# lcdPCB_schematic.net
KiCad netlist of a schematic drawn in EAGLE
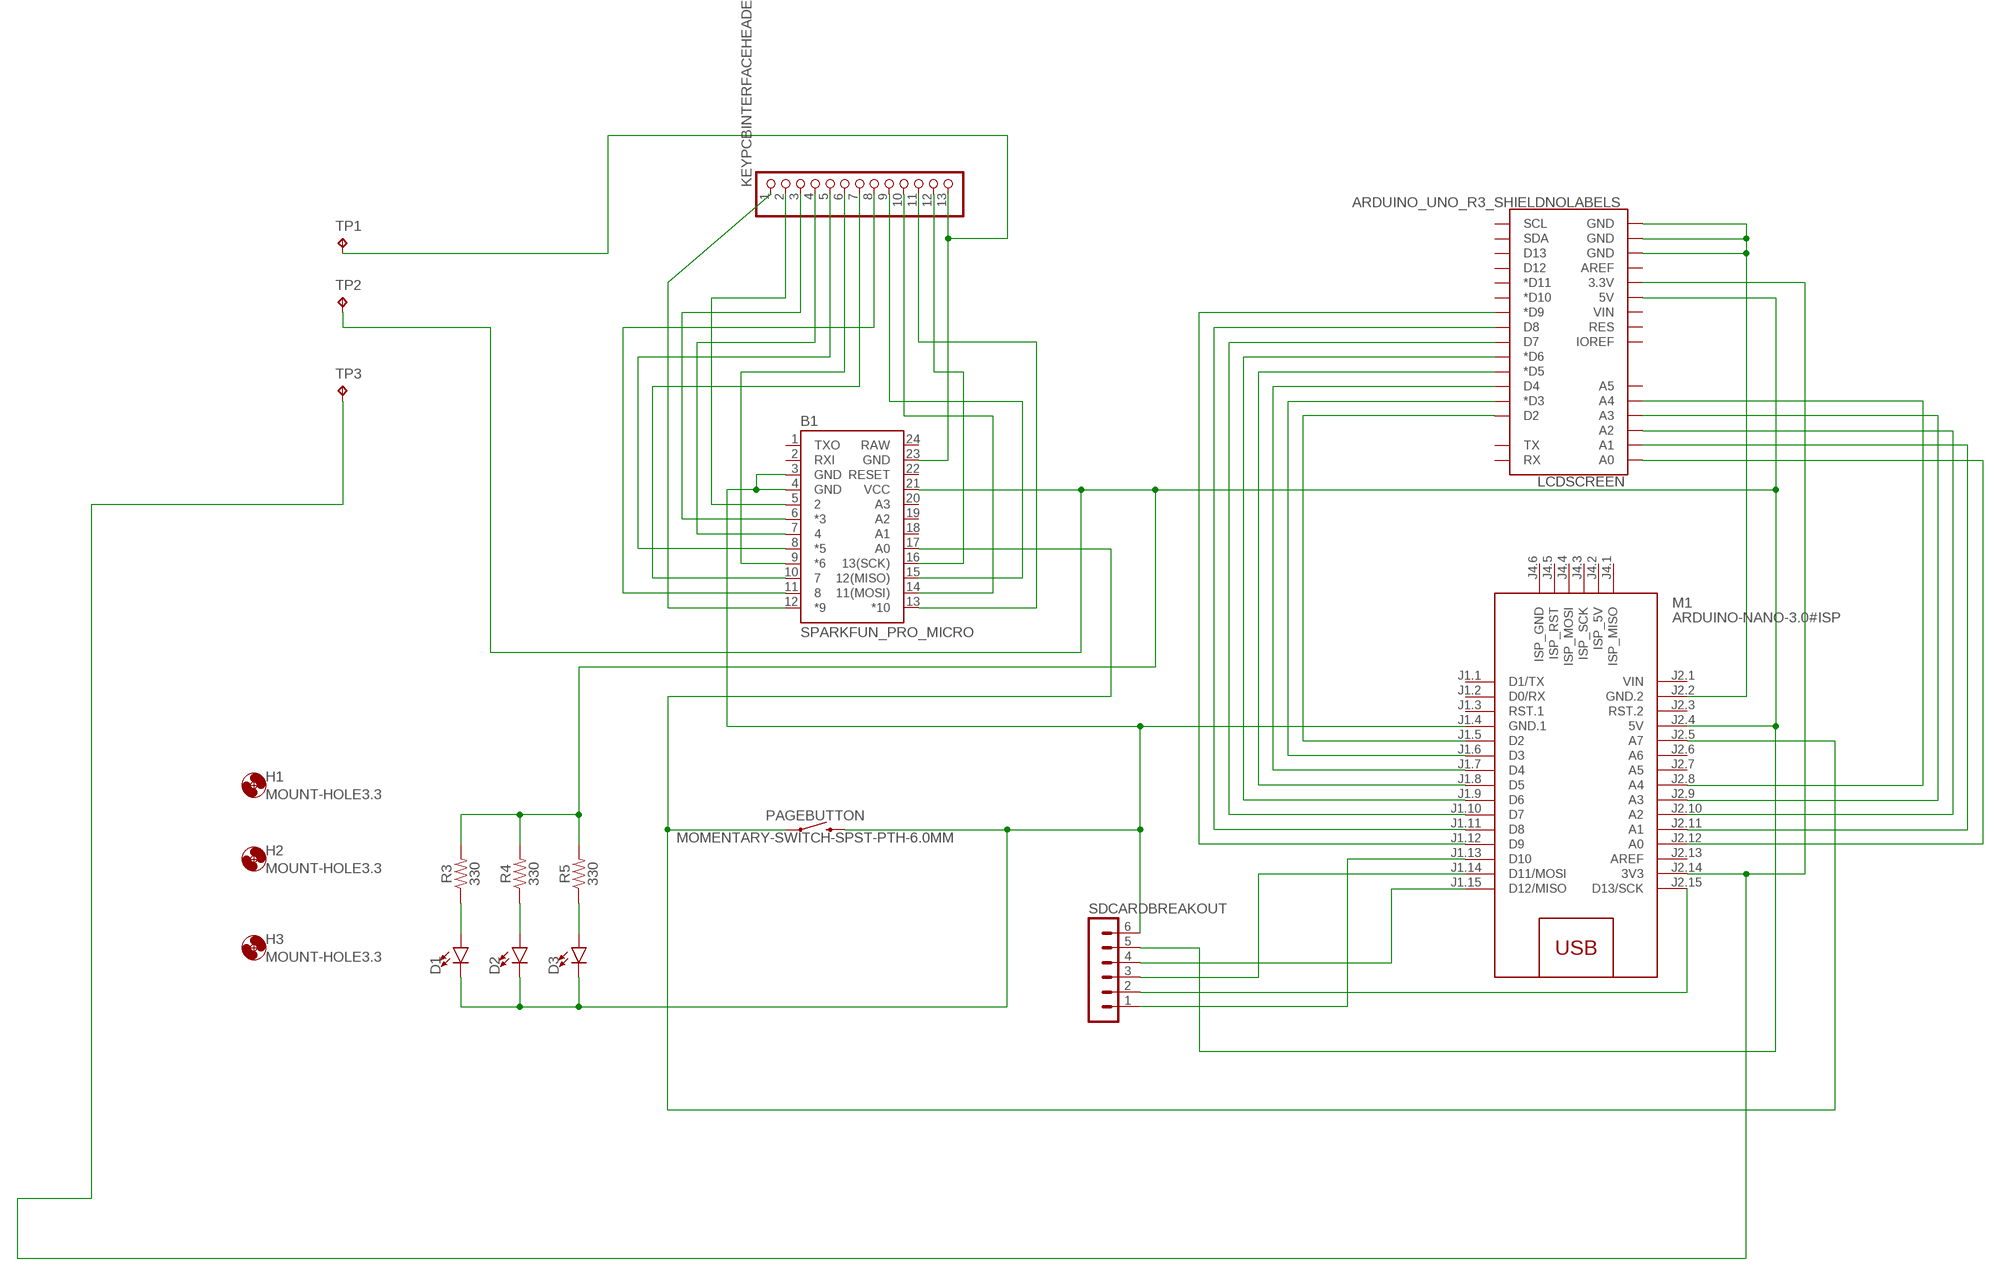
[diagram p0: schematic, sheet 1]

(export (version "E")
  (design (tool "Eeschema 10.0.6"))
  (components
    (comp (ref "B1")
      (value "SPARKFUN_PRO_MICRO")
      (footprint "eagle-import:SPARKFUN_PRO_MICRO")
      (libsource (lib "eagle-import") (part "SPARKFUN_PRO_MICRO"))
    )
    (comp (ref "D1")
      (value "LED-3MM-NO_SILK")
      (footprint "eagle-import:LED_3MM-NS")
      (libsource (lib "eagle-import") (part "LED-3MM-NO_SILK"))
    )
    (comp (ref "D2")
      (value "LED-3MM-NO_SILK")
      (footprint "eagle-import:LED_3MM-NS")
      (libsource (lib "eagle-import") (part "LED-3MM-NO_SILK"))
    )
    (comp (ref "D3")
      (value "LED-3MM-NO_SILK")
      (footprint "eagle-import:LED_3MM-NS")
      (libsource (lib "eagle-import") (part "LED-3MM-NO_SILK"))
    )
    (comp (ref "H1")
      (value "MOUNT-HOLE3.3")
      (footprint "eagle-import:3,3")
      (libsource (lib "eagle-import") (part "MOUNT-HOLE3.3"))
    )
    (comp (ref "H2")
      (value "MOUNT-HOLE3.3")
      (footprint "eagle-import:3,3")
      (libsource (lib "eagle-import") (part "MOUNT-HOLE3.3"))
    )
    (comp (ref "H3")
      (value "MOUNT-HOLE3.3")
      (footprint "eagle-import:3,3")
      (libsource (lib "eagle-import") (part "MOUNT-HOLE3.3"))
    )
    (comp (ref "KEYPCBINTERFACEHEADER")
      (value "PINHD-1X13")
      (footprint "eagle-import:1X13")
      (libsource (lib "eagle-import") (part "PINHD-1X13"))
    )
    (comp (ref "LCDSCREEN")
      (value "ARDUINO_UNO_R3_SHIELDNOLABELS")
      (footprint "eagle-import:UNO_R3_SHIELD_NOLABELS")
      (libsource (lib "eagle-import") (part "ARDUINO_UNO_R3_SHIELDNOLABELS"))
    )
    (comp (ref "M1")
      (value "ARDUINO-NANO-3.0#ISP")
      (footprint "eagle-import:ARDUINO-NANO-3.0#ISP")
      (libsource (lib "eagle-import") (part "ARDUINO-NANO-3.0#ISP"))
    )
    (comp (ref "PAGEBUTTON")
      (value "MOMENTARY-SWITCH-SPST-PTH-6.0MM")
      (footprint "eagle-import:TACTILE_SWITCH_PTH_6.0MM")
      (libsource (lib "eagle-import") (part "MOMENTARY-SWITCH-SPST-PTH-6.0MM"))
    )
    (comp (ref "R3")
      (value "330")
      (footprint "eagle-import:AXIAL-0.3")
      (libsource (lib "eagle-import") (part "330OHM-HORIZ-1/10W-5%"))
    )
    (comp (ref "R4")
      (value "330")
      (footprint "eagle-import:AXIAL-0.3")
      (libsource (lib "eagle-import") (part "330OHM-HORIZ-1/10W-5%"))
    )
    (comp (ref "R5")
      (value "330")
      (footprint "eagle-import:AXIAL-0.3")
      (libsource (lib "eagle-import") (part "330OHM-HORIZ-1/10W-5%"))
    )
    (comp (ref "SDCARDBREAKOUT")
      (value "MA06-1")
      (footprint "eagle-import:MA06-1")
      (libsource (lib "eagle-import") (part "MA06-1"))
    )
    (comp (ref "TP1")
      (value "TPTP20SQ")
      (footprint "eagle-import:TP20SQ")
      (libsource (lib "eagle-import") (part "TPTP20SQ"))
    )
    (comp (ref "TP2")
      (value "TPTP20SQ")
      (footprint "eagle-import:TP20SQ")
      (libsource (lib "eagle-import") (part "TPTP20SQ"))
    )
    (comp (ref "TP3")
      (value "TPTP20SQ")
      (footprint "eagle-import:TP20SQ")
      (libsource (lib "eagle-import") (part "TPTP20SQ"))
    )
  )
  (nets
    (net (code "1") (name "/RAW") (class "Default")
      (node (ref "B1") (pin "24") (pinfunction "RAW_24") (pintype "power_in"))
    )
    (net (code "2") (name "/VIN") (class "Default")
      (node (ref "M1") (pin "J2.1") (pinfunction "VIN_J2.1") (pintype "power_in"))
    )
    (net (code "3") (name "Net-(B1-*3)") (class "Default")
      (node (ref "B1") (pin "6") (pinfunction "*3_6") (pintype "bidirectional"))
      (node (ref "KEYPCBINTERFACEHEADER") (pin "3") (pinfunction "3_3") (pintype "passive"))
    )
    (net (code "4") (name "Net-(B1-*5)") (class "Default")
      (node (ref "B1") (pin "8") (pinfunction "*5_8") (pintype "bidirectional"))
      (node (ref "KEYPCBINTERFACEHEADER") (pin "5") (pinfunction "5_5") (pintype "passive"))
    )
    (net (code "5") (name "Net-(B1-*6)") (class "Default")
      (node (ref "B1") (pin "9") (pinfunction "*6_9") (pintype "bidirectional"))
      (node (ref "KEYPCBINTERFACEHEADER") (pin "6") (pinfunction "6_6") (pintype "passive"))
    )
    (net (code "6") (name "Net-(B1-*9)") (class "Default")
      (node (ref "B1") (pin "12") (pinfunction "*9_12") (pintype "bidirectional"))
      (node (ref "KEYPCBINTERFACEHEADER") (pin "1") (pinfunction "1_1") (pintype "passive"))
    )
    (net (code "7") (name "Net-(B1-*10)") (class "Default")
      (node (ref "B1") (pin "13") (pinfunction "*10_13") (pintype "bidirectional"))
      (node (ref "KEYPCBINTERFACEHEADER") (pin "11") (pinfunction "11_11") (pintype "passive"))
    )
    (net (code "8") (name "Net-(B1-2)") (class "Default")
      (node (ref "B1") (pin "5") (pinfunction "2_5") (pintype "bidirectional"))
      (node (ref "KEYPCBINTERFACEHEADER") (pin "2") (pinfunction "2_2") (pintype "passive"))
    )
    (net (code "9") (name "Net-(B1-4)") (class "Default")
      (node (ref "B1") (pin "7") (pinfunction "4_7") (pintype "bidirectional"))
      (node (ref "KEYPCBINTERFACEHEADER") (pin "4") (pinfunction "4_4") (pintype "passive"))
    )
    (net (code "10") (name "Net-(B1-7)") (class "Default")
      (node (ref "B1") (pin "10") (pinfunction "7_10") (pintype "bidirectional"))
      (node (ref "KEYPCBINTERFACEHEADER") (pin "7") (pinfunction "7_7") (pintype "passive"))
    )
    (net (code "11") (name "Net-(B1-8)") (class "Default")
      (node (ref "B1") (pin "11") (pinfunction "8_11") (pintype "bidirectional"))
      (node (ref "KEYPCBINTERFACEHEADER") (pin "8") (pinfunction "8_8") (pintype "passive"))
    )
    (net (code "12") (name "Net-(B1-11(MOSI))") (class "Default")
      (node (ref "B1") (pin "14") (pinfunction "11(MOSI)_14") (pintype "bidirectional"))
      (node (ref "KEYPCBINTERFACEHEADER") (pin "10") (pinfunction "10_10") (pintype "passive"))
    )
    (net (code "13") (name "Net-(B1-12(MISO))") (class "Default")
      (node (ref "B1") (pin "15") (pinfunction "12(MISO)_15") (pintype "bidirectional"))
      (node (ref "KEYPCBINTERFACEHEADER") (pin "9") (pinfunction "9_9") (pintype "passive"))
    )
    (net (code "14") (name "Net-(B1-13(SCK))") (class "Default")
      (node (ref "B1") (pin "16") (pinfunction "13(SCK)_16") (pintype "bidirectional"))
      (node (ref "KEYPCBINTERFACEHEADER") (pin "12") (pinfunction "12_12") (pintype "passive"))
    )
    (net (code "15") (name "Net-(B1-A0)") (class "Default")
      (node (ref "B1") (pin "17") (pinfunction "A0_17") (pintype "bidirectional"))
      (node (ref "M1") (pin "J2.5") (pinfunction "A7_J2.5") (pintype "bidirectional"))
      (node (ref "PAGEBUTTON") (pin "1") (pinfunction "1_1") (pintype "passive"))
    )
    (net (code "16") (name "Net-(B1-GND-Pad23)") (class "Default")
      (node (ref "B1") (pin "23") (pinfunction "GND_23") (pintype "power_in"))
      (node (ref "KEYPCBINTERFACEHEADER") (pin "13") (pinfunction "13_13") (pintype "passive"))
      (node (ref "TP1") (pin "TP") (pinfunction "TP_TP") (pintype "input"))
    )
    (net (code "17") (name "Net-(B1-VCC)") (class "Default")
      (node (ref "B1") (pin "21") (pinfunction "VCC_21") (pintype "power_in"))
      (node (ref "LCDSCREEN") (pin "5V") (pinfunction "5V_5V") (pintype "bidirectional"))
      (node (ref "M1") (pin "J2.4") (pinfunction "5V_J2.4") (pintype "power_in"))
      (node (ref "R3") (pin "P$2") (pinfunction "2_P$2") (pintype "passive"))
      (node (ref "R4") (pin "P$2") (pinfunction "2_P$2") (pintype "passive"))
      (node (ref "R5") (pin "P$2") (pinfunction "2_P$2") (pintype "passive"))
      (node (ref "SDCARDBREAKOUT") (pin "5") (pinfunction "5_5") (pintype "passive"))
      (node (ref "TP2") (pin "TP") (pinfunction "TP_TP") (pintype "input"))
    )
    (net (code "18") (name "Net-(D1-C)") (class "Default")
      (node (ref "B1") (pin "3") (pinfunction "GND_3") (pintype "power_in"))
      (node (ref "B1") (pin "4") (pinfunction "GND_4") (pintype "power_in"))
      (node (ref "D1") (pin "K") (pinfunction "C_K") (pintype "passive"))
      (node (ref "D2") (pin "K") (pinfunction "C_K") (pintype "passive"))
      (node (ref "D3") (pin "K") (pinfunction "C_K") (pintype "passive"))
      (node (ref "M1") (pin "J1.4") (pinfunction "GND.1_J1.4") (pintype "power_in"))
      (node (ref "PAGEBUTTON") (pin "3") (pinfunction "2_3") (pintype "passive"))
      (node (ref "SDCARDBREAKOUT") (pin "6") (pinfunction "6_6") (pintype "passive"))
    )
    (net (code "19") (name "Net-(LCDSCREEN-*D3)") (class "Default")
      (node (ref "LCDSCREEN") (pin "D3") (pinfunction "*D3_D3") (pintype "bidirectional"))
      (node (ref "M1") (pin "J1.6") (pinfunction "D3_J1.6") (pintype "bidirectional"))
    )
    (net (code "20") (name "Net-(LCDSCREEN-*D5)") (class "Default")
      (node (ref "LCDSCREEN") (pin "D5") (pinfunction "*D5_D5") (pintype "bidirectional"))
      (node (ref "M1") (pin "J1.8") (pinfunction "D5_J1.8") (pintype "bidirectional"))
    )
    (net (code "21") (name "Net-(LCDSCREEN-*D6)") (class "Default")
      (node (ref "LCDSCREEN") (pin "D6") (pinfunction "*D6_D6") (pintype "bidirectional"))
      (node (ref "M1") (pin "J1.9") (pinfunction "D6_J1.9") (pintype "bidirectional"))
    )
    (net (code "22") (name "Net-(LCDSCREEN-*D9)") (class "Default")
      (node (ref "LCDSCREEN") (pin "D9") (pinfunction "*D9_D9") (pintype "bidirectional"))
      (node (ref "M1") (pin "J1.12") (pinfunction "D9_J1.12") (pintype "bidirectional"))
    )
    (net (code "23") (name "Net-(M1-3V3)") (class "Default")
      (node (ref "LCDSCREEN") (pin "3.3V") (pinfunction "3.3V_3.3V") (pintype "bidirectional"))
      (node (ref "M1") (pin "J2.14") (pinfunction "3V3_J2.14") (pintype "power_in"))
      (node (ref "TP3") (pin "TP") (pinfunction "TP_TP") (pintype "input"))
    )
    (net (code "24") (name "Net-(M1-A0)") (class "Default")
      (node (ref "LCDSCREEN") (pin "A0") (pinfunction "A0_A0") (pintype "bidirectional"))
      (node (ref "M1") (pin "J2.12") (pinfunction "A0_J2.12") (pintype "bidirectional"))
    )
    (net (code "25") (name "Net-(M1-A1)") (class "Default")
      (node (ref "LCDSCREEN") (pin "A1") (pinfunction "A1_A1") (pintype "bidirectional"))
      (node (ref "M1") (pin "J2.11") (pinfunction "A1_J2.11") (pintype "bidirectional"))
    )
    (net (code "26") (name "Net-(M1-A2)") (class "Default")
      (node (ref "LCDSCREEN") (pin "A2") (pinfunction "A2_A2") (pintype "bidirectional"))
      (node (ref "M1") (pin "J2.10") (pinfunction "A2_J2.10") (pintype "bidirectional"))
    )
    (net (code "27") (name "Net-(M1-A3)") (class "Default")
      (node (ref "LCDSCREEN") (pin "A3") (pinfunction "A3_A3") (pintype "bidirectional"))
      (node (ref "M1") (pin "J2.9") (pinfunction "A3_J2.9") (pintype "bidirectional"))
    )
    (net (code "28") (name "Net-(M1-A4)") (class "Default")
      (node (ref "LCDSCREEN") (pin "A4") (pinfunction "A4_A4") (pintype "bidirectional"))
      (node (ref "M1") (pin "J2.8") (pinfunction "A4_J2.8") (pintype "bidirectional"))
    )
    (net (code "29") (name "Net-(M1-D2)") (class "Default")
      (node (ref "LCDSCREEN") (pin "D2") (pinfunction "D2_D2") (pintype "bidirectional"))
      (node (ref "M1") (pin "J1.5") (pinfunction "D2_J1.5") (pintype "bidirectional"))
    )
    (net (code "30") (name "Net-(M1-D4)") (class "Default")
      (node (ref "LCDSCREEN") (pin "D4") (pinfunction "D4_D4") (pintype "bidirectional"))
      (node (ref "M1") (pin "J1.7") (pinfunction "D4_J1.7") (pintype "bidirectional"))
    )
    (net (code "31") (name "Net-(M1-D7)") (class "Default")
      (node (ref "LCDSCREEN") (pin "D7") (pinfunction "D7_D7") (pintype "bidirectional"))
      (node (ref "M1") (pin "J1.10") (pinfunction "D7_J1.10") (pintype "bidirectional"))
    )
    (net (code "32") (name "Net-(M1-D8)") (class "Default")
      (node (ref "LCDSCREEN") (pin "D8") (pinfunction "D8_D8") (pintype "bidirectional"))
      (node (ref "M1") (pin "J1.11") (pinfunction "D8_J1.11") (pintype "bidirectional"))
    )
    (net (code "33") (name "Net-(M1-D10)") (class "Default")
      (node (ref "M1") (pin "J1.13") (pinfunction "D10_J1.13") (pintype "bidirectional"))
      (node (ref "SDCARDBREAKOUT") (pin "1") (pinfunction "1_1") (pintype "passive"))
    )
    (net (code "34") (name "Net-(M1-D11{slash}MOSI)") (class "Default")
      (node (ref "M1") (pin "J1.14") (pinfunction "D11/MOSI_J1.14") (pintype "bidirectional"))
      (node (ref "SDCARDBREAKOUT") (pin "3") (pinfunction "3_3") (pintype "passive"))
    )
    (net (code "35") (name "Net-(M1-D12{slash}MISO)") (class "Default")
      (node (ref "M1") (pin "J1.15") (pinfunction "D12/MISO_J1.15") (pintype "bidirectional"))
      (node (ref "SDCARDBREAKOUT") (pin "4") (pinfunction "4_4") (pintype "passive"))
    )
    (net (code "36") (name "Net-(M1-D13{slash}SCK)") (class "Default")
      (node (ref "M1") (pin "J2.15") (pinfunction "D13/SCK_J2.15") (pintype "bidirectional"))
      (node (ref "SDCARDBREAKOUT") (pin "2") (pinfunction "2_2") (pintype "passive"))
    )
    (net (code "37") (name "Net-(M1-GND.2)") (class "Default")
      (node (ref "LCDSCREEN") (pin "GND@0") (pinfunction "GND_GND@0") (pintype "bidirectional"))
      (node (ref "LCDSCREEN") (pin "GND@1") (pinfunction "GND_GND@1") (pintype "bidirectional"))
      (node (ref "LCDSCREEN") (pin "GND@2") (pinfunction "GND_GND@2") (pintype "bidirectional"))
      (node (ref "M1") (pin "J2.2") (pinfunction "GND.2_J2.2") (pintype "power_in"))
    )
    (net (code "38") (name "Net-(R3-1)") (class "Default")
      (node (ref "D1") (pin "A") (pinfunction "A_A") (pintype "passive"))
      (node (ref "R3") (pin "P$1") (pinfunction "1_P$1") (pintype "passive"))
    )
    (net (code "39") (name "Net-(R4-1)") (class "Default")
      (node (ref "D2") (pin "A") (pinfunction "A_A") (pintype "passive"))
      (node (ref "R4") (pin "P$1") (pinfunction "1_P$1") (pintype "passive"))
    )
    (net (code "40") (name "Net-(R5-1)") (class "Default")
      (node (ref "D3") (pin "A") (pinfunction "A_A") (pintype "passive"))
      (node (ref "R5") (pin "P$1") (pinfunction "1_P$1") (pintype "passive"))
    )
    (net (code "41") (name "unconnected-(B1-A1-Pad18)") (class "Default")
      (node (ref "B1") (pin "18") (pinfunction "A1_18") (pintype "bidirectional"))
    )
    (net (code "42") (name "unconnected-(B1-A2-Pad19)") (class "Default")
      (node (ref "B1") (pin "19") (pinfunction "A2_19") (pintype "bidirectional"))
    )
    (net (code "43") (name "unconnected-(B1-A3-Pad20)") (class "Default")
      (node (ref "B1") (pin "20") (pinfunction "A3_20") (pintype "bidirectional"))
    )
    (net (code "44") (name "unconnected-(B1-RESET-Pad22)") (class "Default")
      (node (ref "B1") (pin "22") (pinfunction "RESET_22") (pintype "bidirectional"))
    )
    (net (code "45") (name "unconnected-(B1-RXI-Pad2)") (class "Default")
      (node (ref "B1") (pin "2") (pinfunction "RXI_2") (pintype "bidirectional"))
    )
    (net (code "46") (name "unconnected-(B1-TXO-Pad1)") (class "Default")
      (node (ref "B1") (pin "1") (pinfunction "TXO_1") (pintype "bidirectional"))
    )
    (net (code "47") (name "unconnected-(LCDSCREEN-*D10-PadD10)") (class "Default")
      (node (ref "LCDSCREEN") (pin "D10") (pinfunction "*D10_D10") (pintype "bidirectional"))
    )
    (net (code "48") (name "unconnected-(LCDSCREEN-*D11-PadD11)") (class "Default")
      (node (ref "LCDSCREEN") (pin "D11") (pinfunction "*D11_D11") (pintype "bidirectional"))
    )
    (net (code "49") (name "unconnected-(LCDSCREEN-PadA5)") (class "Default")
      (node (ref "LCDSCREEN") (pin "A5") (pinfunction "A5_A5") (pintype "bidirectional"))
    )
    (net (code "50") (name "unconnected-(LCDSCREEN-PadAREF)") (class "Default")
      (node (ref "LCDSCREEN") (pin "AREF") (pinfunction "AREF_AREF") (pintype "bidirectional"))
    )
    (net (code "51") (name "unconnected-(LCDSCREEN-PadD12)") (class "Default")
      (node (ref "LCDSCREEN") (pin "D12") (pinfunction "D12_D12") (pintype "bidirectional"))
    )
    (net (code "52") (name "unconnected-(LCDSCREEN-PadD13)") (class "Default")
      (node (ref "LCDSCREEN") (pin "D13") (pinfunction "D13_D13") (pintype "bidirectional"))
    )
    (net (code "53") (name "unconnected-(LCDSCREEN-PadIOREF)") (class "Default")
      (node (ref "LCDSCREEN") (pin "IOREF") (pinfunction "IOREF_IOREF") (pintype "bidirectional"))
    )
    (net (code "54") (name "unconnected-(LCDSCREEN-PadRES)") (class "Default")
      (node (ref "LCDSCREEN") (pin "RES") (pinfunction "RES_RES") (pintype "bidirectional"))
    )
    (net (code "55") (name "unconnected-(LCDSCREEN-PadRX)") (class "Default")
      (node (ref "LCDSCREEN") (pin "RX") (pinfunction "RX_RX") (pintype "bidirectional"))
    )
    (net (code "56") (name "unconnected-(LCDSCREEN-PadSCL)") (class "Default")
      (node (ref "LCDSCREEN") (pin "SCL") (pinfunction "SCL_SCL") (pintype "bidirectional"))
    )
    (net (code "57") (name "unconnected-(LCDSCREEN-PadSDA)") (class "Default")
      (node (ref "LCDSCREEN") (pin "SDA") (pinfunction "SDA_SDA") (pintype "bidirectional"))
    )
    (net (code "58") (name "unconnected-(LCDSCREEN-PadTX)") (class "Default")
      (node (ref "LCDSCREEN") (pin "TX") (pinfunction "TX_TX") (pintype "bidirectional"))
    )
    (net (code "59") (name "unconnected-(LCDSCREEN-PadVIN)") (class "Default")
      (node (ref "LCDSCREEN") (pin "VIN") (pinfunction "VIN_VIN") (pintype "bidirectional"))
    )
    (net (code "60") (name "unconnected-(M1-A5-PadJ2.7)") (class "Default")
      (node (ref "M1") (pin "J2.7") (pinfunction "A5_J2.7") (pintype "bidirectional"))
    )
    (net (code "61") (name "unconnected-(M1-A6-PadJ2.6)") (class "Default")
      (node (ref "M1") (pin "J2.6") (pinfunction "A6_J2.6") (pintype "bidirectional"))
    )
    (net (code "62") (name "unconnected-(M1-AREF-PadJ2.13)") (class "Default")
      (node (ref "M1") (pin "J2.13") (pinfunction "AREF_J2.13") (pintype "bidirectional"))
    )
    (net (code "63") (name "unconnected-(M1-D0{slash}RX-PadJ1.2)") (class "Default")
      (node (ref "M1") (pin "J1.2") (pinfunction "D0/RX_J1.2") (pintype "bidirectional"))
    )
    (net (code "64") (name "unconnected-(M1-D1{slash}TX-PadJ1.1)") (class "Default")
      (node (ref "M1") (pin "J1.1") (pinfunction "D1/TX_J1.1") (pintype "bidirectional"))
    )
    (net (code "65") (name "unconnected-(M1-ISP_5V-PadJ4.2)") (class "Default")
      (node (ref "M1") (pin "J4.2") (pinfunction "ISP_5V_J4.2") (pintype "bidirectional"))
    )
    (net (code "66") (name "unconnected-(M1-ISP_GND-PadJ4.6)") (class "Default")
      (node (ref "M1") (pin "J4.6") (pinfunction "ISP_GND_J4.6") (pintype "bidirectional"))
    )
    (net (code "67") (name "unconnected-(M1-ISP_MISO-PadJ4.1)") (class "Default")
      (node (ref "M1") (pin "J4.1") (pinfunction "ISP_MISO_J4.1") (pintype "bidirectional"))
    )
    (net (code "68") (name "unconnected-(M1-ISP_MOSI-PadJ4.4)") (class "Default")
      (node (ref "M1") (pin "J4.4") (pinfunction "ISP_MOSI_J4.4") (pintype "bidirectional"))
    )
    (net (code "69") (name "unconnected-(M1-ISP_RST-PadJ4.5)") (class "Default")
      (node (ref "M1") (pin "J4.5") (pinfunction "ISP_RST_J4.5") (pintype "bidirectional"))
    )
    (net (code "70") (name "unconnected-(M1-ISP_SCK-PadJ4.3)") (class "Default")
      (node (ref "M1") (pin "J4.3") (pinfunction "ISP_SCK_J4.3") (pintype "bidirectional"))
    )
    (net (code "71") (name "unconnected-(M1-RST.1-PadJ1.3)") (class "Default")
      (node (ref "M1") (pin "J1.3") (pinfunction "RST.1_J1.3") (pintype "bidirectional"))
    )
    (net (code "72") (name "unconnected-(M1-RST.2-PadJ2.3)") (class "Default")
      (node (ref "M1") (pin "J2.3") (pinfunction "RST.2_J2.3") (pintype "bidirectional"))
    )
  )
)
